# ICM42605.net
KiCad netlist of a schematic drawn in Altium Designer
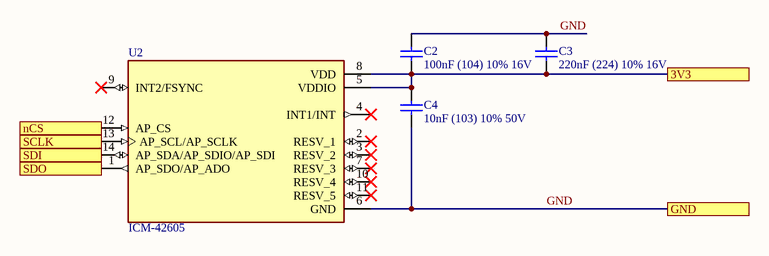
[diagram p0: ICM42605.SchDoc]

(export (version "E")
  (design (tool "Eeschema 10.0.6"))
  (components
    (comp (ref "C2")
      (value "100nF (104) 10% 16V")
      (footprint "0402_C")
      (description "贴片电容")
      (libsource (lib "Miscellaneous Devices LC") (part "0402 100nF (104) 10% 16V"))
    )
    (comp (ref "C3")
      (value "220nF (224) 10% 16V")
      (footprint "0402_C")
      (description "贴片电容")
      (libsource (lib "Miscellaneous Devices LC") (part "0402 220nF (224) 10% 16V"))
    )
    (comp (ref "C4")
      (value "10nF (103) 10% 50V")
      (footprint "0402_C")
      (description "贴片电容")
      (libsource (lib "Miscellaneous Devices LC") (part "0402 10nF (103) 10% 50V"))
    )
    (comp (ref "U2")
      (value "ICM-42605")
      (footprint "PQFN50P300X250X97-14N")
      (description "Accelerometer, Gyroscope, 6 Axis Sensor IÂ²C, I3Câ„ , SPI Output")
      (fields (field (name "DIGI-KEY_PART_NUMBER") "1428-1152-1-ND") (field (name "MF") "TDK InvenSense"))
      (libsource (lib "ICM-42605") (part "ICM-42605"))
    )
  )
  (nets
    (net (code "1") (name "/3V3") (class "Default")
      (node (ref "C2") (pin "1") (pinfunction "1_1") (pintype "passive"))
      (node (ref "C3") (pin "1") (pinfunction "1_1") (pintype "passive"))
      (node (ref "C4") (pin "2") (pinfunction "2_2") (pintype "passive"))
      (node (ref "U2") (pin "5") (pinfunction "VDDIO_5") (pintype "power_in"))
      (node (ref "U2") (pin "8") (pinfunction "VDD_8") (pintype "power_in"))
    )
    (net (code "2") (name "/GND") (class "Default")
      (node (ref "C2") (pin "2") (pinfunction "2_2") (pintype "passive"))
      (node (ref "C3") (pin "2") (pinfunction "2_2") (pintype "passive"))
      (node (ref "C4") (pin "1") (pinfunction "1_1") (pintype "passive"))
      (node (ref "U2") (pin "6") (pinfunction "GND_6") (pintype "power_in"))
    )
    (net (code "3") (name "/SCLK") (class "Default")
      (node (ref "U2") (pin "13") (pinfunction "AP_SCL/AP_SCLK_13") (pintype "input"))
    )
    (net (code "4") (name "/SDI") (class "Default")
      (node (ref "U2") (pin "14") (pinfunction "AP_SDA/AP_SDIO/AP_SDI_14") (pintype "bidirectional"))
    )
    (net (code "5") (name "/SDO") (class "Default")
      (node (ref "U2") (pin "1") (pinfunction "AP_SDO/AP_ADO_1") (pintype "output"))
    )
    (net (code "6") (name "/nCS") (class "Default")
      (node (ref "U2") (pin "12") (pinfunction "AP_CS_12") (pintype "input"))
    )
    (net (code "7") (name "unconnected-(U2-INT1{slash}INT-Pad4)") (class "Default")
      (node (ref "U2") (pin "4") (pinfunction "INT1/INT_4") (pintype "output+no_connect"))
    )
    (net (code "8") (name "unconnected-(U2-INT2{slash}FSYNC-Pad9)") (class "Default")
      (node (ref "U2") (pin "9") (pinfunction "INT2/FSYNC_9") (pintype "bidirectional+no_connect"))
    )
    (net (code "9") (name "unconnected-(U2-RESV_1-Pad2)") (class "Default")
      (node (ref "U2") (pin "2") (pinfunction "RESV_1_2") (pintype "bidirectional+no_connect"))
    )
    (net (code "10") (name "unconnected-(U2-RESV_2-Pad3)") (class "Default")
      (node (ref "U2") (pin "3") (pinfunction "RESV_2_3") (pintype "bidirectional+no_connect"))
    )
    (net (code "11") (name "unconnected-(U2-RESV_3-Pad7)") (class "Default")
      (node (ref "U2") (pin "7") (pinfunction "RESV_3_7") (pintype "bidirectional+no_connect"))
    )
    (net (code "12") (name "unconnected-(U2-RESV_4-Pad10)") (class "Default")
      (node (ref "U2") (pin "10") (pinfunction "RESV_4_10") (pintype "bidirectional+no_connect"))
    )
    (net (code "13") (name "unconnected-(U2-RESV_5-Pad11)") (class "Default")
      (node (ref "U2") (pin "11") (pinfunction "RESV_5_11") (pintype "bidirectional+no_connect"))
    )
  )
)
